# Sheet4.net
KiCad netlist of a schematic drawn in Altium Designer
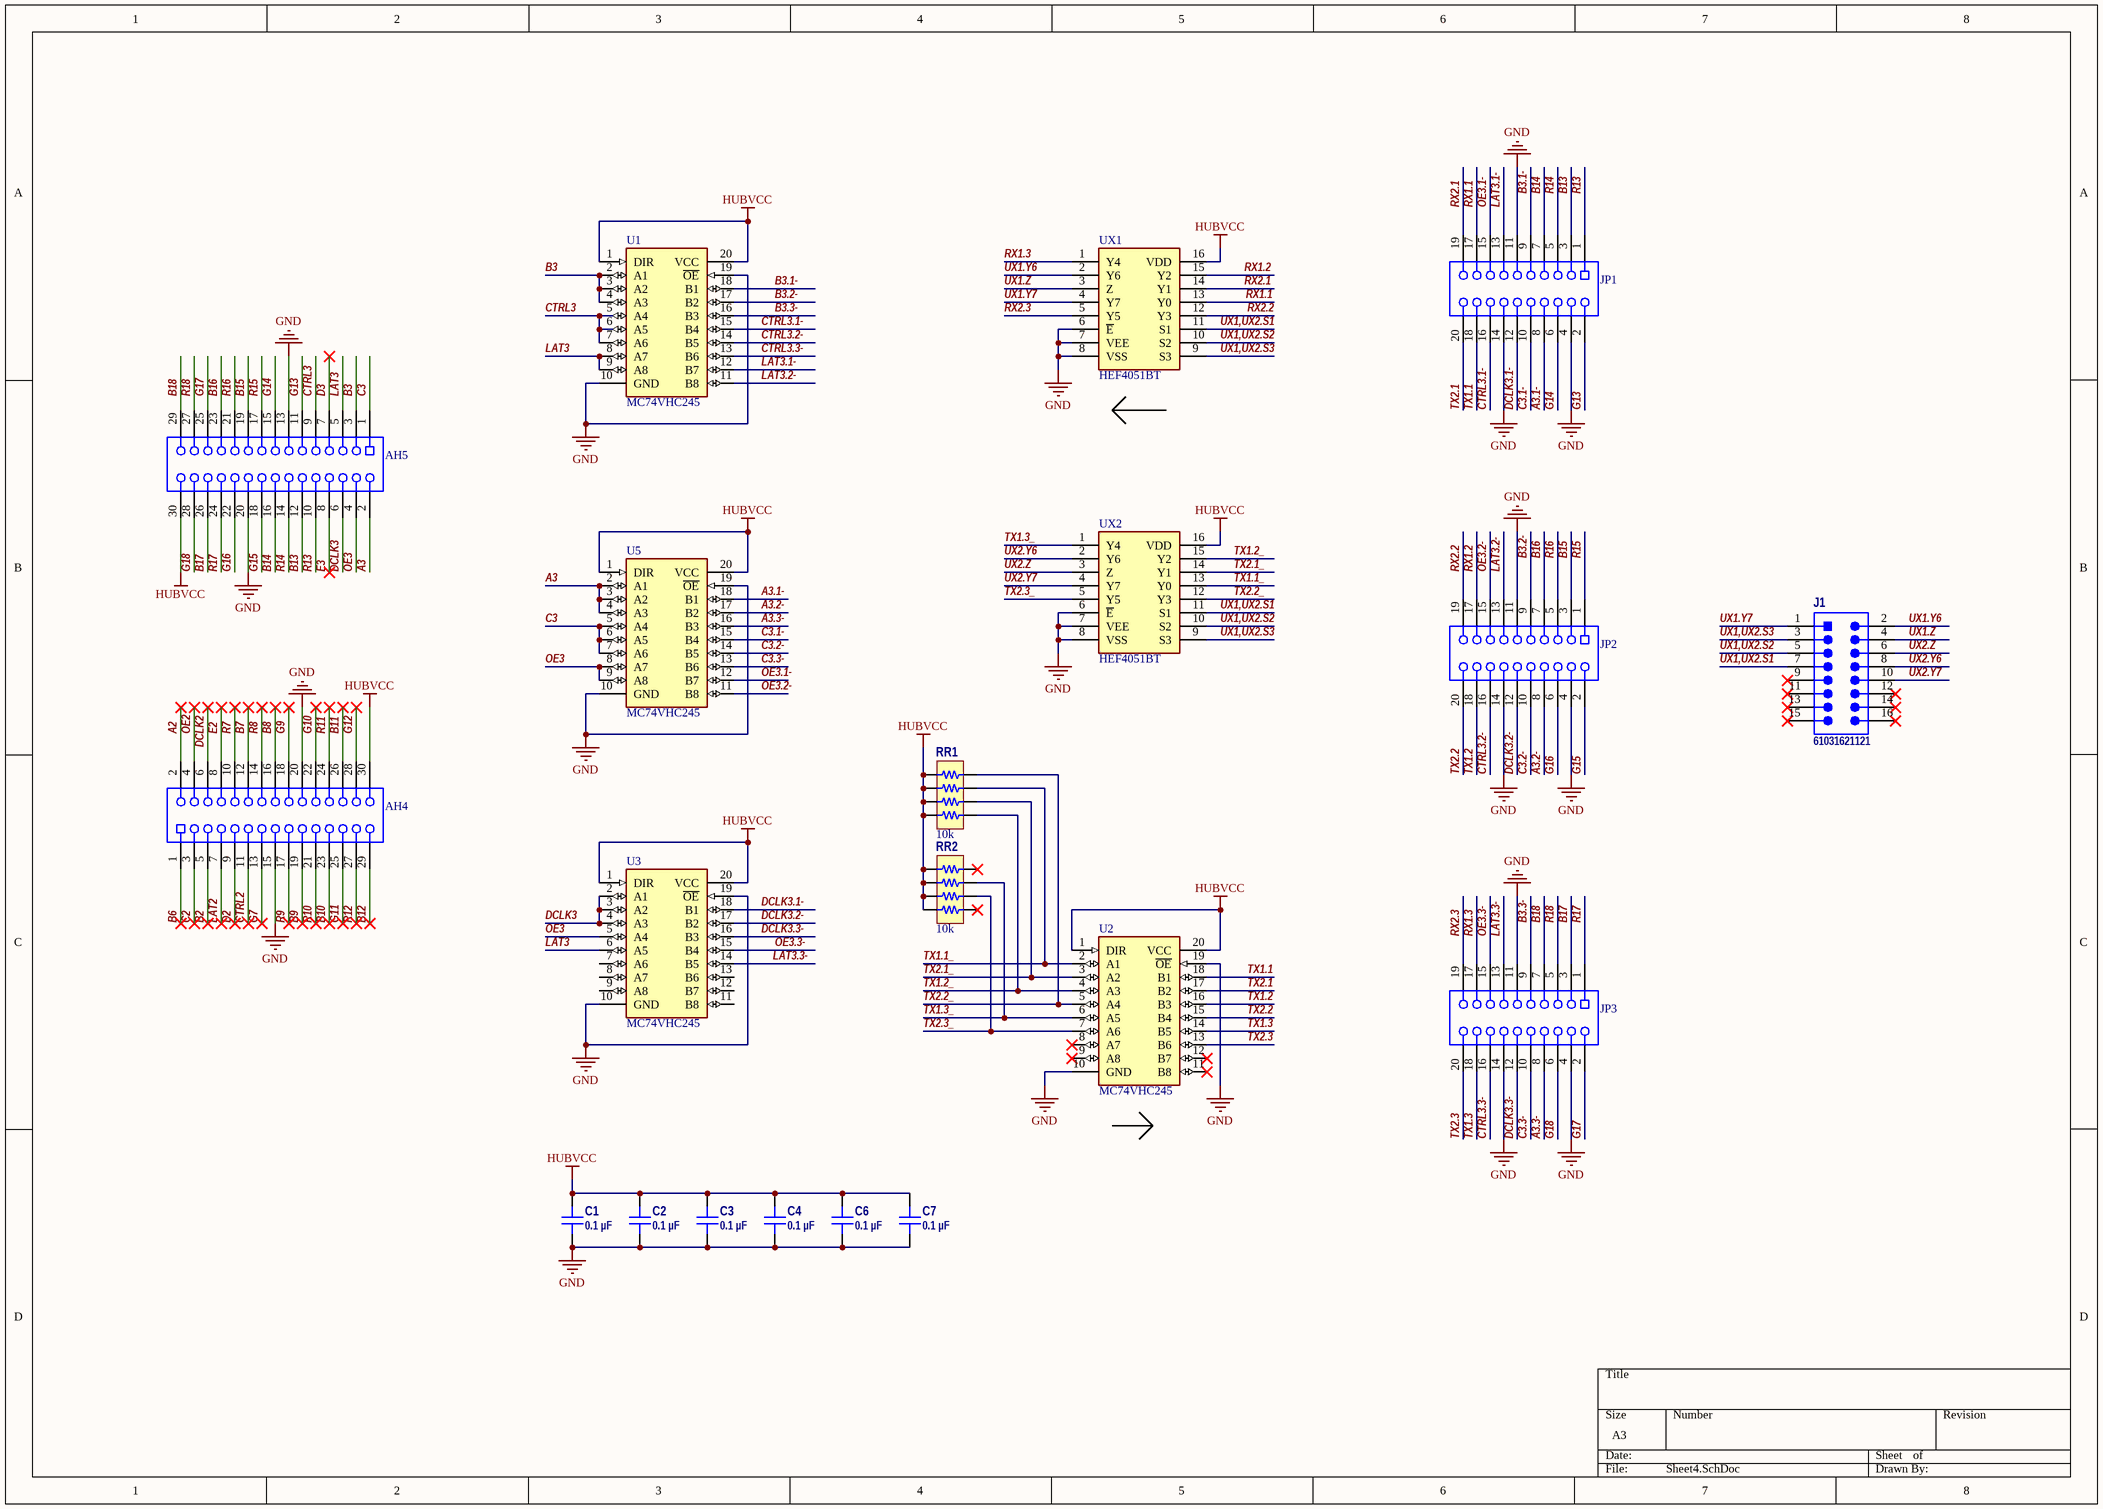
[diagram p0: Sheet4.SchDoc]

(export (version "E")
  (design (tool "Eeschema 10.0.6"))
  (components
    (comp (ref "AH4")
      (value "61003021821")
      (footprint "61003021821")
      (description "WR-PHD Socket Header, SMT, pitch 2.54mm, Dual Row, Vertical, 30p")
      (fields (field (name "MANUFACTURER") "Wurth Elektronik"))
      (libsource (lib "Altium_WR-PHD (rev22a)") (part "61003021821"))
    )
    (comp (ref "AH5")
      (value "61003021821")
      (footprint "61003021821")
      (description "WR-PHD Socket Header, SMT, pitch 2.54mm, Dual Row, Vertical, 30p")
      (fields (field (name "MANUFACTURER") "Wurth Elektronik"))
      (libsource (lib "Altium_WR-PHD (rev22a)") (part "61003021821"))
    )
    (comp (ref "C1")
      (value "0.1 µF")
      (footprint "CAP 0603_1608")
      (description "CAP CER 0.1UF 25V X7R 0603")
      (fields (field (name "PART NUMBER") "CC0603MRX7R8BB104") (field (name "MANUFACTURER") "Yageo"))
      (libsource (lib "Celestial Altium Library - altium_library") (part "Capacitor"))
    )
    (comp (ref "C2")
      (value "0.1 µF")
      (footprint "CAP 0603_1608")
      (description "CAP CER 0.1UF 25V X7R 0603")
      (fields (field (name "PART NUMBER") "CC0603MRX7R8BB104") (field (name "MANUFACTURER") "Yageo"))
      (libsource (lib "Celestial Altium Library - altium_library") (part "Capacitor"))
    )
    (comp (ref "C3")
      (value "0.1 µF")
      (footprint "CAP 0603_1608")
      (description "CAP CER 0.1UF 25V X7R 0603")
      (fields (field (name "PART NUMBER") "CC0603MRX7R8BB104") (field (name "MANUFACTURER") "Yageo"))
      (libsource (lib "Celestial Altium Library - altium_library") (part "Capacitor"))
    )
    (comp (ref "C4")
      (value "0.1 µF")
      (footprint "CAP 0603_1608")
      (description "CAP CER 0.1UF 25V X7R 0603")
      (fields (field (name "PART NUMBER") "CC0603MRX7R8BB104") (field (name "MANUFACTURER") "Yageo"))
      (libsource (lib "Celestial Altium Library - altium_library") (part "Capacitor"))
    )
    (comp (ref "C6")
      (value "0.1 µF")
      (footprint "CAP 0603_1608")
      (description "CAP CER 0.1UF 25V X7R 0603")
      (fields (field (name "PART NUMBER") "CC0603MRX7R8BB104") (field (name "MANUFACTURER") "Yageo"))
      (libsource (lib "Celestial Altium Library - altium_library") (part "Capacitor"))
    )
    (comp (ref "C7")
      (value "0.1 µF")
      (footprint "CAP 0603_1608")
      (description "CAP CER 0.1UF 25V X7R 0603")
      (fields (field (name "PART NUMBER") "CC0603MRX7R8BB104") (field (name "MANUFACTURER") "Yageo"))
      (libsource (lib "Celestial Altium Library - altium_library") (part "Capacitor"))
    )
    (comp (ref "J1")
      (value "61031621121")
      (footprint "61031621121")
      (description "WR-PHD Pin Header, SMT, pitch 2.54mm, Dual Row, Vertical, 16p")
      (fields (field (name "MANUFACTURER") "Wurth Elektronik"))
      (libsource (lib "Altium_WR-PHD (rev22a)") (part "61031621121"))
    )
    (comp (ref "JP1")
      (value "61002021821")
      (footprint "61002021821")
      (description "WR-PHD Socket Header, SMT, pitch 2.54mm, Dual Row, Vertical, 20p")
      (fields (field (name "MANUFACTURER") "Wurth Elektronik"))
      (libsource (lib "Altium_WR-PHD (rev22a)") (part "61002021821"))
    )
    (comp (ref "JP2")
      (value "61002021821")
      (footprint "61002021821")
      (description "WR-PHD Socket Header, SMT, pitch 2.54mm, Dual Row, Vertical, 20p")
      (fields (field (name "MANUFACTURER") "Wurth Elektronik"))
      (libsource (lib "Altium_WR-PHD (rev22a)") (part "61002021821"))
    )
    (comp (ref "JP3")
      (value "61002021821")
      (footprint "61002021821")
      (description "WR-PHD Socket Header, SMT, pitch 2.54mm, Dual Row, Vertical, 20p")
      (fields (field (name "MANUFACTURER") "Wurth Elektronik"))
      (libsource (lib "Altium_WR-PHD (rev22a)") (part "61002021821"))
    )
    (comp (ref "RR1")
      (value "YC124-JR-0710KL")
      (footprint "RESNET 0804-8 CONVEX")
      (description "RES ARRAY 4 RES 10K OHM 0804")
      (fields
        (field (name "MANUFACTURER") "Yageo")
        (field (name "RESISTANCE (OHMS)") "10k")
        (field (name "TOLERANCE") "±5%")
      )
      (libsource (lib "Celestial Altium Library - altium_library") (part "Resistor Array (4 circuit)"))
    )
    (comp (ref "RR2")
      (value "YC124-JR-0710KL")
      (footprint "RESNET 0804-8 CONVEX")
      (description "RES ARRAY 4 RES 10K OHM 0804")
      (fields
        (field (name "MANUFACTURER") "Yageo")
        (field (name "RESISTANCE (OHMS)") "10k")
        (field (name "TOLERANCE") "±5%")
      )
      (libsource (lib "Celestial Altium Library - altium_library") (part "Resistor Array (4 circuit)"))
    )
    (comp (ref "U1")
      (value "MC74VHC245")
      (footprint "SamacSys:SOP65P640X120-20N")
      (description "Integrated Circuit")
      (fields
        (field (name "MANUFACTURER_PART_NUMBER") "MC74VHC245DTG")
        (field (name "MOUSER PART NUMBER") "863-MC74VHC245DTG")
      )
      (libsource (lib "*") (part "MC74VHC245DTG"))
    )
    (comp (ref "U2")
      (value "MC74VHC245")
      (footprint "SamacSys:SOP65P640X120-20N")
      (description "Integrated Circuit")
      (fields
        (field (name "MANUFACTURER_PART_NUMBER") "MC74VHC245DTG")
        (field (name "MOUSER PART NUMBER") "863-MC74VHC245DTG")
      )
      (libsource (lib "*") (part "MC74VHC245DTG"))
    )
    (comp (ref "U3")
      (value "MC74VHC245")
      (footprint "SamacSys:SOP65P640X120-20N")
      (description "Integrated Circuit")
      (fields
        (field (name "MANUFACTURER_PART_NUMBER") "MC74VHC245DTG")
        (field (name "MOUSER PART NUMBER") "863-MC74VHC245DTG")
      )
      (libsource (lib "*") (part "MC74VHC245DTG"))
    )
    (comp (ref "U5")
      (value "MC74VHC245")
      (footprint "SamacSys:SOP65P640X120-20N")
      (description "Integrated Circuit")
      (fields
        (field (name "MANUFACTURER_PART_NUMBER") "MC74VHC245DTG")
        (field (name "MOUSER PART NUMBER") "863-MC74VHC245DTG")
      )
      (libsource (lib "*") (part "MC74VHC245DTG"))
    )
    (comp (ref "UX1")
      (value "HEF4051BT")
      (footprint "SamacSys:SOIC127P600X175-16N")
      (description "Integrated Circuit")
      (libsource (lib "*") (part "HEF4051BT"))
    )
    (comp (ref "UX2")
      (value "HEF4051BT")
      (footprint "SamacSys:SOIC127P600X175-16N")
      (description "Integrated Circuit")
      (libsource (lib "*") (part "HEF4051BT"))
    )
  )
  (nets
    (net (code "1") (name "/A2") (class "Default")
      (node (ref "AH4") (pin "2") (pinfunction "2_2") (pintype "passive+no_connect"))
    )
    (net (code "2") (name "/A3") (class "Default")
      (node (ref "AH5") (pin "2") (pinfunction "2_2") (pintype "passive"))
      (node (ref "U5") (pin "2") (pinfunction "A1_2") (pintype "bidirectional"))
      (node (ref "U5") (pin "3") (pinfunction "A2_3") (pintype "bidirectional"))
      (node (ref "U5") (pin "4") (pinfunction "A3_4") (pintype "bidirectional"))
    )
    (net (code "3") (name "/A3.1-") (class "Default")
      (node (ref "JP1") (pin "8") (pinfunction "8_8") (pintype "passive"))
      (node (ref "U5") (pin "18") (pinfunction "B1_18") (pintype "bidirectional"))
    )
    (net (code "4") (name "/A3.2-") (class "Default")
      (node (ref "JP2") (pin "8") (pinfunction "8_8") (pintype "passive"))
      (node (ref "U5") (pin "17") (pinfunction "B2_17") (pintype "bidirectional"))
    )
    (net (code "5") (name "/A3.3-") (class "Default")
      (node (ref "JP3") (pin "8") (pinfunction "8_8") (pintype "passive"))
      (node (ref "U5") (pin "16") (pinfunction "B3_16") (pintype "bidirectional"))
    )
    (net (code "6") (name "/B2") (class "Default")
      (node (ref "AH4") (pin "5") (pinfunction "5_5") (pintype "passive+no_connect"))
    )
    (net (code "7") (name "/B3") (class "Default")
      (node (ref "AH5") (pin "3") (pinfunction "3_3") (pintype "passive"))
      (node (ref "U1") (pin "2") (pinfunction "A1_2") (pintype "bidirectional"))
      (node (ref "U1") (pin "3") (pinfunction "A2_3") (pintype "bidirectional"))
      (node (ref "U1") (pin "4") (pinfunction "A3_4") (pintype "bidirectional"))
    )
    (net (code "8") (name "/B3.1-") (class "Default")
      (node (ref "JP1") (pin "9") (pinfunction "9_9") (pintype "passive"))
      (node (ref "U1") (pin "18") (pinfunction "B1_18") (pintype "bidirectional"))
    )
    (net (code "9") (name "/B3.2-") (class "Default")
      (node (ref "JP2") (pin "9") (pinfunction "9_9") (pintype "passive"))
      (node (ref "U1") (pin "17") (pinfunction "B2_17") (pintype "bidirectional"))
    )
    (net (code "10") (name "/B3.3-") (class "Default")
      (node (ref "JP3") (pin "9") (pinfunction "9_9") (pintype "passive"))
      (node (ref "U1") (pin "16") (pinfunction "B3_16") (pintype "bidirectional"))
    )
    (net (code "11") (name "/B6") (class "Default")
      (node (ref "AH4") (pin "1") (pinfunction "1_1") (pintype "passive+no_connect"))
    )
    (net (code "12") (name "/B7") (class "Default")
      (node (ref "AH4") (pin "12") (pinfunction "12_12") (pintype "passive+no_connect"))
    )
    (net (code "13") (name "/B8") (class "Default")
      (node (ref "AH4") (pin "16") (pinfunction "16_16") (pintype "passive+no_connect"))
    )
    (net (code "14") (name "/B9") (class "Default")
      (node (ref "AH4") (pin "19") (pinfunction "19_19") (pintype "passive+no_connect"))
    )
    (net (code "15") (name "/B10") (class "Default")
      (node (ref "AH4") (pin "23") (pinfunction "23_23") (pintype "passive+no_connect"))
    )
    (net (code "16") (name "/B11") (class "Default")
      (node (ref "AH4") (pin "26") (pinfunction "26_26") (pintype "passive+no_connect"))
    )
    (net (code "17") (name "/B12") (class "Default")
      (node (ref "AH4") (pin "29") (pinfunction "29_29") (pintype "passive+no_connect"))
    )
    (net (code "18") (name "/B13") (class "Default")
      (node (ref "AH5") (pin "12") (pinfunction "12_12") (pintype "passive"))
      (node (ref "JP1") (pin "3") (pinfunction "3_3") (pintype "passive"))
    )
    (net (code "19") (name "/B14") (class "Default")
      (node (ref "AH5") (pin "16") (pinfunction "16_16") (pintype "passive"))
      (node (ref "JP1") (pin "7") (pinfunction "7_7") (pintype "passive"))
    )
    (net (code "20") (name "/B15") (class "Default")
      (node (ref "AH5") (pin "19") (pinfunction "19_19") (pintype "passive"))
      (node (ref "JP2") (pin "3") (pinfunction "3_3") (pintype "passive"))
    )
    (net (code "21") (name "/B16") (class "Default")
      (node (ref "AH5") (pin "23") (pinfunction "23_23") (pintype "passive"))
      (node (ref "JP2") (pin "7") (pinfunction "7_7") (pintype "passive"))
    )
    (net (code "22") (name "/B17") (class "Default")
      (node (ref "AH5") (pin "26") (pinfunction "26_26") (pintype "passive"))
      (node (ref "JP3") (pin "3") (pinfunction "3_3") (pintype "passive"))
    )
    (net (code "23") (name "/B18") (class "Default")
      (node (ref "AH5") (pin "29") (pinfunction "29_29") (pintype "passive"))
      (node (ref "JP3") (pin "7") (pinfunction "7_7") (pintype "passive"))
    )
    (net (code "24") (name "/C2") (class "Default")
      (node (ref "AH4") (pin "3") (pinfunction "3_3") (pintype "passive+no_connect"))
    )
    (net (code "25") (name "/C3") (class "Default")
      (node (ref "AH5") (pin "1") (pinfunction "1_1") (pintype "passive"))
      (node (ref "U5") (pin "5") (pinfunction "A4_5") (pintype "bidirectional"))
      (node (ref "U5") (pin "6") (pinfunction "A5_6") (pintype "bidirectional"))
      (node (ref "U5") (pin "7") (pinfunction "A6_7") (pintype "bidirectional"))
    )
    (net (code "26") (name "/C3.1-") (class "Default")
      (node (ref "JP1") (pin "10") (pinfunction "10_10") (pintype "passive"))
      (node (ref "U5") (pin "15") (pinfunction "B4_15") (pintype "bidirectional"))
    )
    (net (code "27") (name "/C3.2-") (class "Default")
      (node (ref "JP2") (pin "10") (pinfunction "10_10") (pintype "passive"))
      (node (ref "U5") (pin "14") (pinfunction "B5_14") (pintype "bidirectional"))
    )
    (net (code "28") (name "/C3.3-") (class "Default")
      (node (ref "JP3") (pin "10") (pinfunction "10_10") (pintype "passive"))
      (node (ref "U5") (pin "13") (pinfunction "B6_13") (pintype "bidirectional"))
    )
    (net (code "29") (name "/CTRL2") (class "Default")
      (node (ref "AH4") (pin "11") (pinfunction "11_11") (pintype "passive+no_connect"))
    )
    (net (code "30") (name "/CTRL3") (class "Default")
      (node (ref "AH5") (pin "9") (pinfunction "9_9") (pintype "passive"))
      (node (ref "U1") (pin "5") (pinfunction "A4_5") (pintype "bidirectional"))
      (node (ref "U1") (pin "6") (pinfunction "A5_6") (pintype "bidirectional"))
      (node (ref "U1") (pin "7") (pinfunction "A6_7") (pintype "bidirectional"))
    )
    (net (code "31") (name "/CTRL3.1-") (class "Default")
      (node (ref "JP1") (pin "16") (pinfunction "16_16") (pintype "passive"))
      (node (ref "U1") (pin "15") (pinfunction "B4_15") (pintype "bidirectional"))
    )
    (net (code "32") (name "/CTRL3.2-") (class "Default")
      (node (ref "JP2") (pin "16") (pinfunction "16_16") (pintype "passive"))
      (node (ref "U1") (pin "14") (pinfunction "B5_14") (pintype "bidirectional"))
    )
    (net (code "33") (name "/CTRL3.3-") (class "Default")
      (node (ref "JP3") (pin "16") (pinfunction "16_16") (pintype "passive"))
      (node (ref "U1") (pin "13") (pinfunction "B6_13") (pintype "bidirectional"))
    )
    (net (code "34") (name "/D2") (class "Default")
      (node (ref "AH4") (pin "9") (pinfunction "9_9") (pintype "passive+no_connect"))
    )
    (net (code "35") (name "/D3") (class "Default")
      (node (ref "AH5") (pin "7") (pinfunction "7_7") (pintype "passive+no_connect"))
    )
    (net (code "36") (name "/DCLK2") (class "Default")
      (node (ref "AH4") (pin "6") (pinfunction "6_6") (pintype "passive+no_connect"))
    )
    (net (code "37") (name "/DCLK3") (class "Default")
      (node (ref "AH5") (pin "6") (pinfunction "6_6") (pintype "passive"))
      (node (ref "U3") (pin "2") (pinfunction "A1_2") (pintype "bidirectional"))
      (node (ref "U3") (pin "3") (pinfunction "A2_3") (pintype "bidirectional"))
      (node (ref "U3") (pin "4") (pinfunction "A3_4") (pintype "bidirectional"))
    )
    (net (code "38") (name "/DCLK3.1-") (class "Default")
      (node (ref "JP1") (pin "12") (pinfunction "12_12") (pintype "passive"))
      (node (ref "U3") (pin "18") (pinfunction "B1_18") (pintype "bidirectional"))
    )
    (net (code "39") (name "/DCLK3.2-") (class "Default")
      (node (ref "JP2") (pin "12") (pinfunction "12_12") (pintype "passive"))
      (node (ref "U3") (pin "17") (pinfunction "B2_17") (pintype "bidirectional"))
    )
    (net (code "40") (name "/DCLK3.3-") (class "Default")
      (node (ref "JP3") (pin "12") (pinfunction "12_12") (pintype "passive"))
      (node (ref "U3") (pin "16") (pinfunction "B3_16") (pintype "bidirectional"))
    )
    (net (code "41") (name "/E2") (class "Default")
      (node (ref "AH4") (pin "8") (pinfunction "8_8") (pintype "passive+no_connect"))
    )
    (net (code "42") (name "/E3") (class "Default")
      (node (ref "AH5") (pin "8") (pinfunction "8_8") (pintype "passive+no_connect"))
    )
    (net (code "43") (name "/G7") (class "Default")
      (node (ref "AH4") (pin "13") (pinfunction "13_13") (pintype "passive+no_connect"))
    )
    (net (code "44") (name "/G9") (class "Default")
      (node (ref "AH4") (pin "18") (pinfunction "18_18") (pintype "passive+no_connect"))
    )
    (net (code "45") (name "/G10") (class "Default")
      (node (ref "AH4") (pin "22") (pinfunction "22_22") (pintype "passive+no_connect"))
    )
    (net (code "46") (name "/G11") (class "Default")
      (node (ref "AH4") (pin "25") (pinfunction "25_25") (pintype "passive+no_connect"))
    )
    (net (code "47") (name "/G12") (class "Default")
      (node (ref "AH4") (pin "28") (pinfunction "28_28") (pintype "passive+no_connect"))
    )
    (net (code "48") (name "/G13") (class "Default")
      (node (ref "AH5") (pin "11") (pinfunction "11_11") (pintype "passive"))
      (node (ref "JP1") (pin "2") (pinfunction "2_2") (pintype "passive"))
    )
    (net (code "49") (name "/G14") (class "Default")
      (node (ref "AH5") (pin "15") (pinfunction "15_15") (pintype "passive"))
      (node (ref "JP1") (pin "6") (pinfunction "6_6") (pintype "passive"))
    )
    (net (code "50") (name "/G15") (class "Default")
      (node (ref "AH5") (pin "18") (pinfunction "18_18") (pintype "passive"))
      (node (ref "JP2") (pin "2") (pinfunction "2_2") (pintype "passive"))
    )
    (net (code "51") (name "/G16") (class "Default")
      (node (ref "AH5") (pin "22") (pinfunction "22_22") (pintype "passive"))
      (node (ref "JP2") (pin "6") (pinfunction "6_6") (pintype "passive"))
    )
    (net (code "52") (name "/G17") (class "Default")
      (node (ref "AH5") (pin "25") (pinfunction "25_25") (pintype "passive"))
      (node (ref "JP3") (pin "2") (pinfunction "2_2") (pintype "passive"))
    )
    (net (code "53") (name "/G18") (class "Default")
      (node (ref "AH5") (pin "28") (pinfunction "28_28") (pintype "passive"))
      (node (ref "JP3") (pin "6") (pinfunction "6_6") (pintype "passive"))
    )
    (net (code "54") (name "/LAT2") (class "Default")
      (node (ref "AH4") (pin "7") (pinfunction "7_7") (pintype "passive+no_connect"))
    )
    (net (code "55") (name "/LAT3") (class "Default")
      (node (ref "AH5") (pin "5") (pinfunction "5_5") (pintype "passive"))
      (node (ref "U1") (pin "8") (pinfunction "A7_8") (pintype "bidirectional"))
      (node (ref "U1") (pin "9") (pinfunction "A8_9") (pintype "bidirectional"))
      (node (ref "U3") (pin "6") (pinfunction "A5_6") (pintype "bidirectional"))
    )
    (net (code "56") (name "/LAT3.1-") (class "Default")
      (node (ref "JP1") (pin "13") (pinfunction "13_13") (pintype "passive"))
      (node (ref "U1") (pin "12") (pinfunction "B7_12") (pintype "bidirectional"))
    )
    (net (code "57") (name "/LAT3.2-") (class "Default")
      (node (ref "JP2") (pin "13") (pinfunction "13_13") (pintype "passive"))
      (node (ref "U1") (pin "11") (pinfunction "B8_11") (pintype "bidirectional"))
    )
    (net (code "58") (name "/LAT3.3-") (class "Default")
      (node (ref "JP3") (pin "13") (pinfunction "13_13") (pintype "passive"))
      (node (ref "U3") (pin "14") (pinfunction "B5_14") (pintype "bidirectional"))
    )
    (net (code "59") (name "/OE2") (class "Default")
      (node (ref "AH4") (pin "4") (pinfunction "4_4") (pintype "passive+no_connect"))
    )
    (net (code "60") (name "/OE3") (class "Default")
      (node (ref "AH5") (pin "4") (pinfunction "4_4") (pintype "passive"))
      (node (ref "U3") (pin "5") (pinfunction "A4_5") (pintype "bidirectional"))
      (node (ref "U5") (pin "8") (pinfunction "A7_8") (pintype "bidirectional"))
      (node (ref "U5") (pin "9") (pinfunction "A8_9") (pintype "bidirectional"))
    )
    (net (code "61") (name "/OE3.1-") (class "Default")
      (node (ref "JP1") (pin "15") (pinfunction "15_15") (pintype "passive"))
      (node (ref "U5") (pin "12") (pinfunction "B7_12") (pintype "bidirectional"))
    )
    (net (code "62") (name "/OE3.2-") (class "Default")
      (node (ref "JP2") (pin "15") (pinfunction "15_15") (pintype "passive"))
      (node (ref "U5") (pin "11") (pinfunction "B8_11") (pintype "bidirectional"))
    )
    (net (code "63") (name "/OE3.3-") (class "Default")
      (node (ref "JP3") (pin "15") (pinfunction "15_15") (pintype "passive"))
      (node (ref "U3") (pin "15") (pinfunction "B4_15") (pintype "bidirectional"))
    )
    (net (code "64") (name "/R7") (class "Default")
      (node (ref "AH4") (pin "10") (pinfunction "10_10") (pintype "passive+no_connect"))
    )
    (net (code "65") (name "/R8") (class "Default")
      (node (ref "AH4") (pin "14") (pinfunction "14_14") (pintype "passive+no_connect"))
    )
    (net (code "66") (name "/R9") (class "Default")
      (node (ref "AH4") (pin "17") (pinfunction "17_17") (pintype "passive+no_connect"))
    )
    (net (code "67") (name "/R10") (class "Default")
      (node (ref "AH4") (pin "21") (pinfunction "21_21") (pintype "passive+no_connect"))
    )
    (net (code "68") (name "/R11") (class "Default")
      (node (ref "AH4") (pin "24") (pinfunction "24_24") (pintype "passive+no_connect"))
    )
    (net (code "69") (name "/R12") (class "Default")
      (node (ref "AH4") (pin "27") (pinfunction "27_27") (pintype "passive+no_connect"))
    )
    (net (code "70") (name "/R13") (class "Default")
      (node (ref "AH5") (pin "10") (pinfunction "10_10") (pintype "passive"))
      (node (ref "JP1") (pin "1") (pinfunction "1_1") (pintype "passive"))
    )
    (net (code "71") (name "/R14") (class "Default")
      (node (ref "AH5") (pin "14") (pinfunction "14_14") (pintype "passive"))
      (node (ref "JP1") (pin "5") (pinfunction "5_5") (pintype "passive"))
    )
    (net (code "72") (name "/R15") (class "Default")
      (node (ref "AH5") (pin "17") (pinfunction "17_17") (pintype "passive"))
      (node (ref "JP2") (pin "1") (pinfunction "1_1") (pintype "passive"))
    )
    (net (code "73") (name "/R16") (class "Default")
      (node (ref "AH5") (pin "21") (pinfunction "21_21") (pintype "passive"))
      (node (ref "JP2") (pin "5") (pinfunction "5_5") (pintype "passive"))
    )
    (net (code "74") (name "/R17") (class "Default")
      (node (ref "AH5") (pin "24") (pinfunction "24_24") (pintype "passive"))
      (node (ref "JP3") (pin "1") (pinfunction "1_1") (pintype "passive"))
    )
    (net (code "75") (name "/R18") (class "Default")
      (node (ref "AH5") (pin "27") (pinfunction "27_27") (pintype "passive"))
      (node (ref "JP3") (pin "5") (pinfunction "5_5") (pintype "passive"))
    )
    (net (code "76") (name "/RX1.1") (class "Default")
      (node (ref "JP1") (pin "17") (pinfunction "17_17") (pintype "passive"))
      (node (ref "UX1") (pin "13") (pinfunction "Y0_13") (pintype "passive"))
    )
    (net (code "77") (name "/RX1.2") (class "Default")
      (node (ref "JP2") (pin "17") (pinfunction "17_17") (pintype "passive"))
      (node (ref "UX1") (pin "15") (pinfunction "Y2_15") (pintype "passive"))
    )
    (net (code "78") (name "/RX1.3") (class "Default")
      (node (ref "JP3") (pin "17") (pinfunction "17_17") (pintype "passive"))
      (node (ref "UX1") (pin "1") (pinfunction "Y4_1") (pintype "passive"))
    )
    (net (code "79") (name "/RX2.1") (class "Default")
      (node (ref "JP1") (pin "19") (pinfunction "19_19") (pintype "passive"))
      (node (ref "UX1") (pin "14") (pinfunction "Y1_14") (pintype "passive"))
    )
    (net (code "80") (name "/RX2.2") (class "Default")
      (node (ref "JP2") (pin "19") (pinfunction "19_19") (pintype "passive"))
      (node (ref "UX1") (pin "12") (pinfunction "Y3_12") (pintype "passive"))
    )
    (net (code "81") (name "/RX2.3") (class "Default")
      (node (ref "JP3") (pin "19") (pinfunction "19_19") (pintype "passive"))
      (node (ref "UX1") (pin "5") (pinfunction "Y5_5") (pintype "passive"))
    )
    (net (code "82") (name "/TX1.1") (class "Default")
      (node (ref "JP1") (pin "18") (pinfunction "18_18") (pintype "passive"))
      (node (ref "U2") (pin "18") (pinfunction "B1_18") (pintype "bidirectional"))
    )
    (net (code "83") (name "/TX1.1_") (class "Default")
      (node (ref "RR1") (pin "3") (pinfunction "3_3") (pintype "passive"))
      (node (ref "U2") (pin "2") (pinfunction "A1_2") (pintype "bidirectional"))
      (node (ref "UX2") (pin "13") (pinfunction "Y0_13") (pintype "passive"))
    )
    (net (code "84") (name "/TX1.2") (class "Default")
      (node (ref "JP2") (pin "18") (pinfunction "18_18") (pintype "passive"))
      (node (ref "U2") (pin "16") (pinfunction "B3_16") (pintype "bidirectional"))
    )
    (net (code "85") (name "/TX1.2_") (class "Default")
      (node (ref "RR1") (pin "1") (pinfunction "1_1") (pintype "passive"))
      (node (ref "U2") (pin "4") (pinfunction "A3_4") (pintype "bidirectional"))
      (node (ref "UX2") (pin "15") (pinfunction "Y2_15") (pintype "passive"))
    )
    (net (code "86") (name "/TX1.3") (class "Default")
      (node (ref "JP3") (pin "18") (pinfunction "18_18") (pintype "passive"))
      (node (ref "U2") (pin "14") (pinfunction "B5_14") (pintype "bidirectional"))
    )
    (net (code "87") (name "/TX1.3_") (class "Default")
      (node (ref "RR2") (pin "3") (pinfunction "3_3") (pintype "passive"))
      (node (ref "U2") (pin "6") (pinfunction "A5_6") (pintype "bidirectional"))
      (node (ref "UX2") (pin "1") (pinfunction "Y4_1") (pintype "passive"))
    )
    (net (code "88") (name "/TX2.1") (class "Default")
      (node (ref "JP1") (pin "20") (pinfunction "20_20") (pintype "passive"))
      (node (ref "U2") (pin "17") (pinfunction "B2_17") (pintype "bidirectional"))
    )
    (net (code "89") (name "/TX2.1_") (class "Default")
      (node (ref "RR1") (pin "2") (pinfunction "2_2") (pintype "passive"))
      (node (ref "U2") (pin "3") (pinfunction "A2_3") (pintype "bidirectional"))
      (node (ref "UX2") (pin "14") (pinfunction "Y1_14") (pintype "passive"))
    )
    (net (code "90") (name "/TX2.2") (class "Default")
      (node (ref "JP2") (pin "20") (pinfunction "20_20") (pintype "passive"))
      (node (ref "U2") (pin "15") (pinfunction "B4_15") (pintype "bidirectional"))
    )
    (net (code "91") (name "/TX2.2_") (class "Default")
      (node (ref "RR1") (pin "4") (pinfunction "4_4") (pintype "passive"))
      (node (ref "U2") (pin "5") (pinfunction "A4_5") (pintype "bidirectional"))
      (node (ref "UX2") (pin "12") (pinfunction "Y3_12") (pintype "passive"))
    )
    (net (code "92") (name "/TX2.3") (class "Default")
      (node (ref "JP3") (pin "20") (pinfunction "20_20") (pintype "passive"))
      (node (ref "U2") (pin "13") (pinfunction "B6_13") (pintype "bidirectional"))
    )
    (net (code "93") (name "/TX2.3_") (class "Default")
      (node (ref "RR2") (pin "2") (pinfunction "2_2") (pintype "passive"))
      (node (ref "U2") (pin "7") (pinfunction "A6_7") (pintype "bidirectional"))
      (node (ref "UX2") (pin "5") (pinfunction "Y5_5") (pintype "passive"))
    )
    (net (code "94") (name "/UX1,UX2.S1") (class "Default")
      (node (ref "J1") (pin "7") (pinfunction "7_7") (pintype "passive"))
      (node (ref "UX1") (pin "11") (pinfunction "S1_11") (pintype "passive"))
      (node (ref "UX2") (pin "11") (pinfunction "S1_11") (pintype "passive"))
    )
    (net (code "95") (name "/UX1,UX2.S2") (class "Default")
      (node (ref "J1") (pin "5") (pinfunction "5_5") (pintype "passive"))
      (node (ref "UX1") (pin "10") (pinfunction "S2_10") (pintype "passive"))
      (node (ref "UX2") (pin "10") (pinfunction "S2_10") (pintype "passive"))
    )
    (net (code "96") (name "/UX1,UX2.S3") (class "Default")
      (node (ref "J1") (pin "3") (pinfunction "3_3") (pintype "passive"))
      (node (ref "UX1") (pin "9") (pinfunction "S3_9") (pintype "passive"))
      (node (ref "UX2") (pin "9") (pinfunction "S3_9") (pintype "passive"))
    )
    (net (code "97") (name "/UX1.Y6") (class "Default")
      (node (ref "J1") (pin "2") (pinfunction "2_2") (pintype "passive"))
      (node (ref "UX1") (pin "2") (pinfunction "Y6_2") (pintype "passive"))
    )
    (net (code "98") (name "/UX1.Y7") (class "Default")
      (node (ref "J1") (pin "1") (pinfunction "1_1") (pintype "passive"))
      (node (ref "UX1") (pin "4") (pinfunction "Y7_4") (pintype "passive"))
    )
    (net (code "99") (name "/UX1.Z") (class "Default")
      (node (ref "J1") (pin "4") (pinfunction "4_4") (pintype "passive"))
      (node (ref "UX1") (pin "3") (pinfunction "Z_3") (pintype "passive"))
    )
    (net (code "100") (name "/UX2.Y6") (class "Default")
      (node (ref "J1") (pin "8") (pinfunction "8_8") (pintype "passive"))
      (node (ref "UX2") (pin "2") (pinfunction "Y6_2") (pintype "passive"))
    )
    (net (code "101") (name "/UX2.Y7") (class "Default")
      (node (ref "J1") (pin "10") (pinfunction "10_10") (pintype "passive"))
      (node (ref "UX2") (pin "4") (pinfunction "Y7_4") (pintype "passive"))
    )
    (net (code "102") (name "/UX2.Z") (class "Default")
      (node (ref "J1") (pin "6") (pinfunction "6_6") (pintype "passive"))
      (node (ref "UX2") (pin "3") (pinfunction "Z_3") (pintype "passive"))
    )
    (net (code "103") (name "GND") (class "Default")
      (node (ref "AH4") (pin "15") (pinfunction "15_15") (pintype "passive"))
      (node (ref "AH4") (pin "20") (pinfunction "20_20") (pintype "passive"))
      (node (ref "AH5") (pin "13") (pinfunction "13_13") (pintype "passive"))
      (node (ref "AH5") (pin "20") (pinfunction "20_20") (pintype "passive"))
      (node (ref "C1") (pin "2") (pinfunction "2_2") (pintype "passive"))
      (node (ref "C2") (pin "2") (pinfunction "2_2") (pintype "passive"))
      (node (ref "C3") (pin "2") (pinfunction "2_2") (pintype "passive"))
      (node (ref "C4") (pin "2") (pinfunction "2_2") (pintype "passive"))
      (node (ref "C6") (pin "2") (pinfunction "2_2") (pintype "passive"))
      (node (ref "C7") (pin "2") (pinfunction "2_2") (pintype "passive"))
      (node (ref "JP1") (pin "11") (pinfunction "11_11") (pintype "passive"))
      (node (ref "JP1") (pin "14") (pinfunction "14_14") (pintype "passive"))
      (node (ref "JP1") (pin "4") (pinfunction "4_4") (pintype "passive"))
      (node (ref "JP2") (pin "11") (pinfunction "11_11") (pintype "passive"))
      (node (ref "JP2") (pin "14") (pinfunction "14_14") (pintype "passive"))
      (node (ref "JP2") (pin "4") (pinfunction "4_4") (pintype "passive"))
      (node (ref "JP3") (pin "11") (pinfunction "11_11") (pintype "passive"))
      (node (ref "JP3") (pin "14") (pinfunction "14_14") (pintype "passive"))
      (node (ref "JP3") (pin "4") (pinfunction "4_4") (pintype "passive"))
      (node (ref "U1") (pin "10") (pinfunction "GND_10") (pintype "power_in"))
      (node (ref "U1") (pin "19") (pinfunction "~{OE}_19") (pintype "input"))
      (node (ref "U2") (pin "10") (pinfunction "GND_10") (pintype "power_in"))
      (node (ref "U2") (pin "19") (pinfunction "~{OE}_19") (pintype "input"))
      (node (ref "U3") (pin "10") (pinfunction "GND_10") (pintype "power_in"))
      (node (ref "U3") (pin "19") (pinfunction "~{OE}_19") (pintype "input"))
      (node (ref "U5") (pin "10") (pinfunction "GND_10") (pintype "power_in"))
      (node (ref "U5") (pin "19") (pinfunction "~{OE}_19") (pintype "input"))
      (node (ref "UX1") (pin "6") (pinfunction "~{E}_6") (pintype "passive"))
      (node (ref "UX1") (pin "7") (pinfunction "VEE_7") (pintype "passive"))
      (node (ref "UX1") (pin "8") (pinfunction "VSS_8") (pintype "passive"))
      (node (ref "UX2") (pin "6") (pinfunction "~{E}_6") (pintype "passive"))
      (node (ref "UX2") (pin "7") (pinfunction "VEE_7") (pintype "passive"))
      (node (ref "UX2") (pin "8") (pinfunction "VSS_8") (pintype "passive"))
    )
    (net (code "104") (name "HUBVCC") (class "Default")
      (node (ref "AH4") (pin "30") (pinfunction "30_30") (pintype "passive"))
      (node (ref "AH5") (pin "30") (pinfunction "30_30") (pintype "passive"))
      (node (ref "C1") (pin "1") (pinfunction "1_1") (pintype "passive"))
      (node (ref "C2") (pin "1") (pinfunction "1_1") (pintype "passive"))
      (node (ref "C3") (pin "1") (pinfunction "1_1") (pintype "passive"))
      (node (ref "C4") (pin "1") (pinfunction "1_1") (pintype "passive"))
      (node (ref "C6") (pin "1") (pinfunction "1_1") (pintype "passive"))
      (node (ref "C7") (pin "1") (pinfunction "1_1") (pintype "passive"))
      (node (ref "RR1") (pin "5") (pinfunction "5_5") (pintype "passive"))
      (node (ref "RR1") (pin "6") (pinfunction "6_6") (pintype "passive"))
      (node (ref "RR1") (pin "7") (pinfunction "7_7") (pintype "passive"))
      (node (ref "RR1") (pin "8") (pinfunction "8_8") (pintype "passive"))
      (node (ref "RR2") (pin "5") (pinfunction "5_5") (pintype "passive"))
      (node (ref "RR2") (pin "6") (pinfunction "6_6") (pintype "passive"))
      (node (ref "RR2") (pin "7") (pinfunction "7_7") (pintype "passive"))
      (node (ref "RR2") (pin "8") (pinfunction "8_8") (pintype "passive"))
      (node (ref "U1") (pin "1") (pinfunction "DIR_1") (pintype "input"))
      (node (ref "U1") (pin "20") (pinfunction "VCC_20") (pintype "power_in"))
      (node (ref "U2") (pin "1") (pinfunction "DIR_1") (pintype "input"))
      (node (ref "U2") (pin "20") (pinfunction "VCC_20") (pintype "power_in"))
      (node (ref "U3") (pin "1") (pinfunction "DIR_1") (pintype "input"))
      (node (ref "U3") (pin "20") (pinfunction "VCC_20") (pintype "power_in"))
      (node (ref "U5") (pin "1") (pinfunction "DIR_1") (pintype "input"))
      (node (ref "U5") (pin "20") (pinfunction "VCC_20") (pintype "power_in"))
      (node (ref "UX1") (pin "16") (pinfunction "VDD_16") (pintype "passive"))
      (node (ref "UX2") (pin "16") (pinfunction "VDD_16") (pintype "passive"))
    )
    (net (code "105") (name "unconnected-(J1-Pad9)") (class "Default")
      (node (ref "J1") (pin "9") (pinfunction "9_9") (pintype "passive+no_connect"))
    )
    (net (code "106") (name "unconnected-(J1-Pad11)") (class "Default")
      (node (ref "J1") (pin "11") (pinfunction "11_11") (pintype "passive+no_connect"))
    )
    (net (code "107") (name "unconnected-(J1-Pad12)") (class "Default")
      (node (ref "J1") (pin "12") (pinfunction "12_12") (pintype "passive+no_connect"))
    )
    (net (code "108") (name "unconnected-(J1-Pad13)") (class "Default")
      (node (ref "J1") (pin "13") (pinfunction "13_13") (pintype "passive+no_connect"))
    )
    (net (code "109") (name "unconnected-(J1-Pad14)") (class "Default")
      (node (ref "J1") (pin "14") (pinfunction "14_14") (pintype "passive+no_connect"))
    )
    (net (code "110") (name "unconnected-(J1-Pad15)") (class "Default")
      (node (ref "J1") (pin "15") (pinfunction "15_15") (pintype "passive+no_connect"))
    )
    (net (code "111") (name "unconnected-(J1-Pad16)") (class "Default")
      (node (ref "J1") (pin "16") (pinfunction "16_16") (pintype "passive+no_connect"))
    )
    (net (code "112") (name "unconnected-(RR2-Pad1)") (class "Default")
      (node (ref "RR2") (pin "1") (pinfunction "1_1") (pintype "passive+no_connect"))
    )
    (net (code "113") (name "unconnected-(RR2-Pad4)") (class "Default")
      (node (ref "RR2") (pin "4") (pinfunction "4_4") (pintype "passive+no_connect"))
    )
    (net (code "114") (name "unconnected-(U2-A7-Pad8)") (class "Default")
      (node (ref "U2") (pin "8") (pinfunction "A7_8") (pintype "bidirectional+no_connect"))
    )
    (net (code "115") (name "unconnected-(U2-A8-Pad9)") (class "Default")
      (node (ref "U2") (pin "9") (pinfunction "A8_9") (pintype "bidirectional+no_connect"))
    )
    (net (code "116") (name "unconnected-(U2-B7-Pad12)") (class "Default")
      (node (ref "U2") (pin "12") (pinfunction "B7_12") (pintype "bidirectional+no_connect"))
    )
    (net (code "117") (name "unconnected-(U2-B8-Pad11)") (class "Default")
      (node (ref "U2") (pin "11") (pinfunction "B8_11") (pintype "bidirectional+no_connect"))
    )
    (net (code "118") (name "unconnected-(U3-A6-Pad7)") (class "Default")
      (node (ref "U3") (pin "7") (pinfunction "A6_7") (pintype "bidirectional"))
    )
    (net (code "119") (name "unconnected-(U3-A7-Pad8)") (class "Default")
      (node (ref "U3") (pin "8") (pinfunction "A7_8") (pintype "bidirectional"))
    )
    (net (code "120") (name "unconnected-(U3-A8-Pad9)") (class "Default")
      (node (ref "U3") (pin "9") (pinfunction "A8_9") (pintype "bidirectional"))
    )
    (net (code "121") (name "unconnected-(U3-B6-Pad13)") (class "Default")
      (node (ref "U3") (pin "13") (pinfunction "B6_13") (pintype "bidirectional"))
    )
    (net (code "122") (name "unconnected-(U3-B7-Pad12)") (class "Default")
      (node (ref "U3") (pin "12") (pinfunction "B7_12") (pintype "bidirectional"))
    )
    (net (code "123") (name "unconnected-(U3-B8-Pad11)") (class "Default")
      (node (ref "U3") (pin "11") (pinfunction "B8_11") (pintype "bidirectional"))
    )
  )
)
